# PSU_VCC5V_Buck.net
KiCad netlist of a schematic drawn in Altium Designer
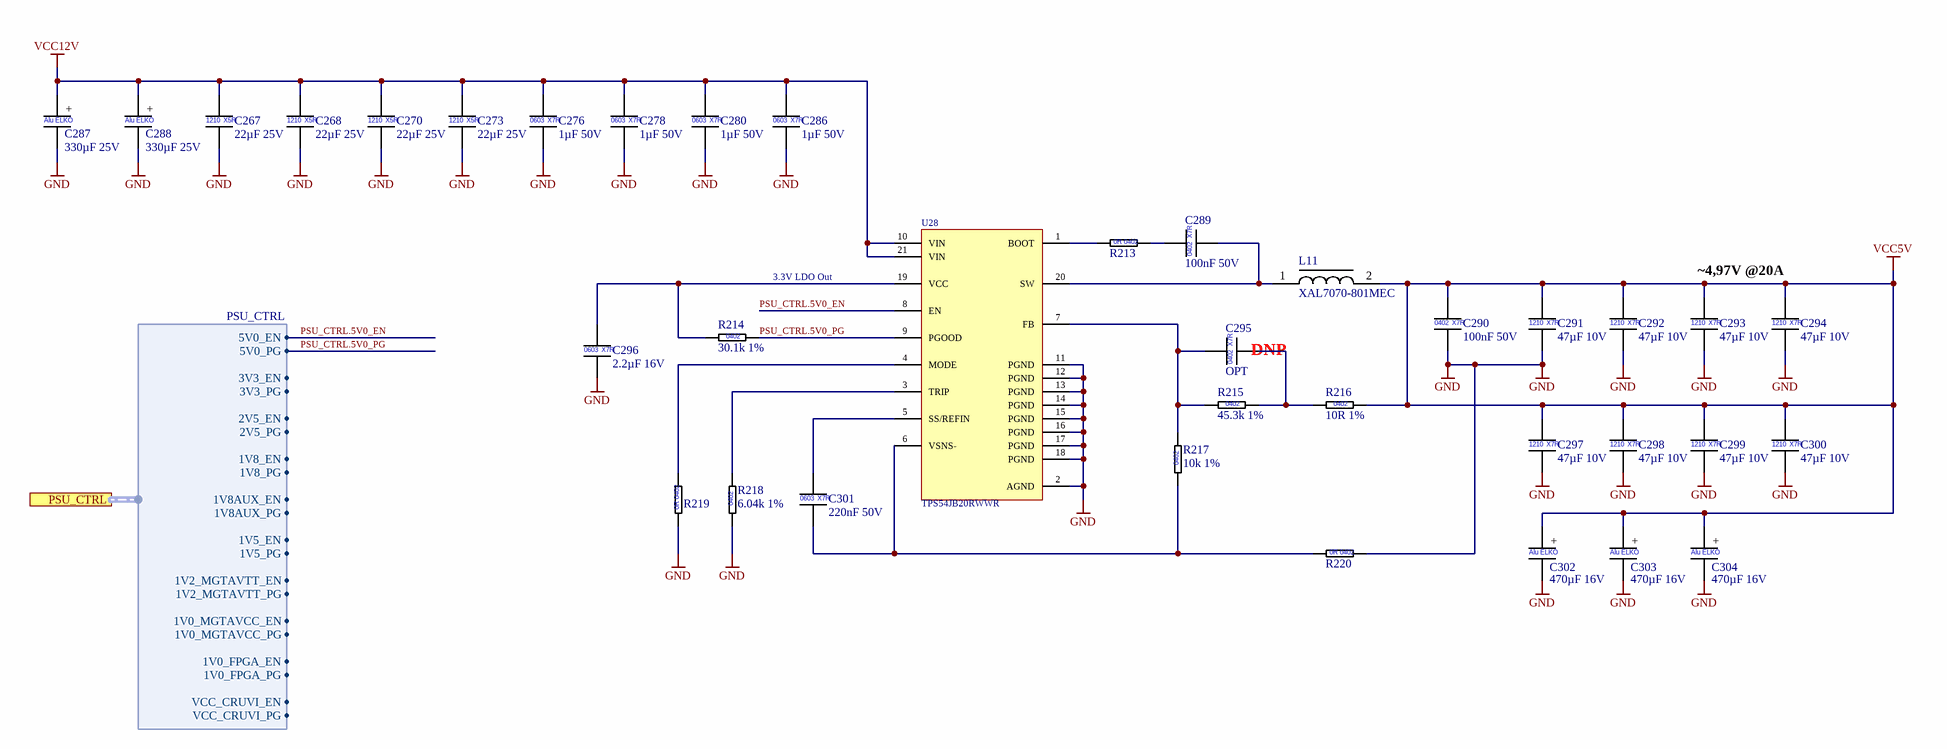
[diagram p0: PSU_VCC5V_Buck.SchDoc]

(export (version "E")
  (design (tool "Eeschema 10.0.6"))
  (components
    (comp (ref "C267")
      (value "22µF 25V")
      (footprint "Cap:CAP_1210")
      (description "Multilayer Ceramic Capacitors MLCC - SMD/SMT 1210 25VDC")
      (libsource (lib "Cap") (part "CAP_1210_22µF_25V"))
    )
    (comp (ref "C268")
      (value "22µF 25V")
      (footprint "Cap:CAP_1210")
      (description "Multilayer Ceramic Capacitors MLCC - SMD/SMT 1210 25VDC")
      (libsource (lib "Cap") (part "CAP_1210_22µF_25V"))
    )
    (comp (ref "C270")
      (value "22µF 25V")
      (footprint "Cap:CAP_1210")
      (description "Multilayer Ceramic Capacitors MLCC - SMD/SMT 1210 25VDC")
      (libsource (lib "Cap") (part "CAP_1210_22µF_25V"))
    )
    (comp (ref "C273")
      (value "22µF 25V")
      (footprint "Cap:CAP_1210")
      (description "Multilayer Ceramic Capacitors MLCC - SMD/SMT 1210 25VDC")
      (libsource (lib "Cap") (part "CAP_1210_22µF_25V"))
    )
    (comp (ref "C276")
      (value "1µF 50V")
      (footprint "CAP_0603")
      (description "Multilayer Ceramic Capacitors MLCC - SMD/SMT 50V 1uF X7R 0603 10%")
      (libsource (lib "Cap") (part "CAP_0603_1µF_50V_X7R_10%"))
    )
    (comp (ref "C278")
      (value "1µF 50V")
      (footprint "CAP_0603")
      (description "Multilayer Ceramic Capacitors MLCC - SMD/SMT 50V 1uF X7R 0603 10%")
      (libsource (lib "Cap") (part "CAP_0603_1µF_50V_X7R_10%"))
    )
    (comp (ref "C280")
      (value "1µF 50V")
      (footprint "CAP_0603")
      (description "Multilayer Ceramic Capacitors MLCC - SMD/SMT 50V 1uF X7R 0603 10%")
      (libsource (lib "Cap") (part "CAP_0603_1µF_50V_X7R_10%"))
    )
    (comp (ref "C286")
      (value "1µF 50V")
      (footprint "CAP_0603")
      (description "Multilayer Ceramic Capacitors MLCC - SMD/SMT 50V 1uF X7R 0603 10%")
      (libsource (lib "Cap") (part "CAP_0603_1µF_50V_X7R_10%"))
    )
    (comp (ref "C287")
      (value "330µF 25V")
      (footprint "Cap:WCAP-PTG5_D10H12.5")
      (description "Organische Polymer-Aluminiumkondensatoren 330uF 25 Volts 20% AEC-Q200")
      (libsource (lib "Cap") (part "CAP_D10L12.5_330µF_25V"))
    )
    (comp (ref "C288")
      (value "330µF 25V")
      (footprint "Cap:WCAP-PTG5_D10H12.5")
      (description "Organische Polymer-Aluminiumkondensatoren 330uF 25 Volts 20% AEC-Q200")
      (libsource (lib "Cap") (part "CAP_D10L12.5_330µF_25V"))
    )
    (comp (ref "C289")
      (value "100nF 50V")
      (footprint "Cap:CAP_0402")
      (description "Multilayer Ceramic Capacitors MLCC - SMD/SMT 0402 50VDC")
      (libsource (lib "") (part "CAP_0402_100nF_50V_1"))
    )
    (comp (ref "C290")
      (value "100nF 50V")
      (footprint "Cap:CAP_0402")
      (description "Multilayer Ceramic Capacitors MLCC - SMD/SMT 0402 50VDC")
      (libsource (lib "Cap") (part "CAP_0402_100nF_50V"))
    )
    (comp (ref "C291")
      (value "47µF 10V")
      (footprint "Cap:CAP_1210")
      (description "Multilayer Ceramic Capacitors MLCC - SMD/SMT 47 uF 10 VDC 10% 1210 X7R")
      (libsource (lib "Cap") (part "CAP_1210_47µF_10V_X7R_10%"))
    )
    (comp (ref "C292")
      (value "47µF 10V")
      (footprint "Cap:CAP_1210")
      (description "Multilayer Ceramic Capacitors MLCC - SMD/SMT 47 uF 10 VDC 10% 1210 X7R")
      (libsource (lib "Cap") (part "CAP_1210_47µF_10V_X7R_10%"))
    )
    (comp (ref "C293")
      (value "47µF 10V")
      (footprint "Cap:CAP_1210")
      (description "Multilayer Ceramic Capacitors MLCC - SMD/SMT 47 uF 10 VDC 10% 1210 X7R")
      (libsource (lib "Cap") (part "CAP_1210_47µF_10V_X7R_10%"))
    )
    (comp (ref "C294")
      (value "47µF 10V")
      (footprint "Cap:CAP_1210")
      (description "Multilayer Ceramic Capacitors MLCC - SMD/SMT 47 uF 10 VDC 10% 1210 X7R")
      (libsource (lib "Cap") (part "CAP_1210_47µF_10V_X7R_10%"))
    )
    (comp (ref "C295")
      (value "OPT")
      (footprint "Cap:CAP_0402")
      (description "Multilayer Ceramic Capacitors MLCC - SMD/SMT 0402 Optional Placeholder")
      (libsource (lib "Cap") (part "CAP_0402_OPT"))
    )
    (comp (ref "C296")
      (value "2.2µF 16V")
      (footprint "Cap:CAP_0603")
      (description "Multilayer Ceramic Capacitors MLCC - SMD/SMT 2.2 uF 16 VDC 10% 0603 X7R")
      (libsource (lib "Cap") (part "CAP_0603_2.2µF_16V_X7R_10%"))
    )
    (comp (ref "C297")
      (value "47µF 10V")
      (footprint "Cap:CAP_1210")
      (description "Multilayer Ceramic Capacitors MLCC - SMD/SMT 47 uF 10 VDC 10% 1210 X7R")
      (libsource (lib "Cap") (part "CAP_1210_47µF_10V_X7R_10%"))
    )
    (comp (ref "C298")
      (value "47µF 10V")
      (footprint "Cap:CAP_1210")
      (description "Multilayer Ceramic Capacitors MLCC - SMD/SMT 47 uF 10 VDC 10% 1210 X7R")
      (libsource (lib "Cap") (part "CAP_1210_47µF_10V_X7R_10%"))
    )
    (comp (ref "C299")
      (value "47µF 10V")
      (footprint "Cap:CAP_1210")
      (description "Multilayer Ceramic Capacitors MLCC - SMD/SMT 47 uF 10 VDC 10% 1210 X7R")
      (libsource (lib "Cap") (part "CAP_1210_47µF_10V_X7R_10%"))
    )
    (comp (ref "C300")
      (value "47µF 10V")
      (footprint "Cap:CAP_1210")
      (description "Multilayer Ceramic Capacitors MLCC - SMD/SMT 47 uF 10 VDC 10% 1210 X7R")
      (libsource (lib "Cap") (part "CAP_1210_47µF_10V_X7R_10%"))
    )
    (comp (ref "C301")
      (value "220nF 50V")
      (footprint "CAP_0603")
      (description "Multilayer Ceramic Capacitors MLCC - SMD/SMT 0.22 uF 50 VDC 10% 0603 X7R")
      (libsource (lib "Cap") (part "CAP_0603_220nF_50V_X7R_10%"))
    )
    (comp (ref "C302")
      (value "470µF 16V")
      (footprint "Cap:WCAP-PTG5_D8H13")
      (description "Organische Polymer-Aluminiumkondensatoren 470uF 16 Volts 20%")
      (libsource (lib "Cap") (part "CAP_D8L9_470µF_16V"))
    )
    (comp (ref "C303")
      (value "470µF 16V")
      (footprint "Cap:WCAP-PTG5_D8H13")
      (description "Organische Polymer-Aluminiumkondensatoren 470uF 16 Volts 20%")
      (libsource (lib "Cap") (part "CAP_D8L9_470µF_16V"))
    )
    (comp (ref "C304")
      (value "470µF 16V")
      (footprint "Cap:WCAP-PTG5_D8H13")
      (description "Organische Polymer-Aluminiumkondensatoren 470uF 16 Volts 20%")
      (libsource (lib "Cap") (part "CAP_D8L9_470µF_16V"))
    )
    (comp (ref "L11")
      (value "XAL7070-801MEC")
      (footprint "indc:COILCRAFT_XAL7070")
      (description "Power Inductors - SMD 800nH Shld 20% 25.8A 2.29mOhms AECQ200")
      (libsource (lib "Indc") (part "XAL7070-801MEC_Power Inductors SMD 800nH Shld 20% 25.8A 2.29mOhms AECQ200"))
    )
    (comp (ref "R213")
      (value "0R Jumper")
      (footprint "res:RES_0402")
      (description "Thick Film Resistors - SMD 0Ohm")
      (libsource (lib "Res") (part "RES_0402_0R Jumper"))
    )
    (comp (ref "R214")
      (value "30.1k 1%")
      (footprint "res:RES_0402")
      (description "Thick Film Resistors - SMD 30.1kOhm 1%")
      (libsource (lib "Res") (part "RES_0402_30.1k_1%"))
    )
    (comp (ref "R215")
      (value "45.3k 1%")
      (footprint "res:RES_0402")
      (description "Thick Film Resistors - SMD 45.3kOhm 1%")
      (libsource (lib "Res") (part "RES_0402_45.3k_1%"))
    )
    (comp (ref "R216")
      (value "10R 1%")
      (footprint "res:RES_0402")
      (description "Thick Film Resistors - SMD 10Ohm 1%")
      (libsource (lib "Res") (part "RES_0402_10R_1%"))
    )
    (comp (ref "R217")
      (value "10k 1%")
      (footprint "Res:RES_0402")
      (description "Thick Film Resistors - SMD 10kOhm 1%")
      (libsource (lib "Res") (part "RES_0402_10k_1%"))
    )
    (comp (ref "R218")
      (value "6.04k 1%")
      (footprint "Res:RES_0402")
      (description "Thick Film Resistors - SMD 6.04kOhm 1%")
      (libsource (lib "Res") (part "RES_0402_6.04k_1%"))
    )
    (comp (ref "R219")
      (value "0R Jumper")
      (footprint "res:RES_0402")
      (description "Thick Film Resistors - SMD 0Ohm")
      (libsource (lib "Res") (part "RES_0402_0R Jumper"))
    )
    (comp (ref "R220")
      (value "0R Jumper")
      (footprint "res:RES_0402")
      (description "Thick Film Resistors - SMD 0Ohm")
      (libsource (lib "Res") (part "RES_0402_0R Jumper"))
    )
    (comp (ref "U28")
      (value "TPS54JB20RWWR")
      (footprint "power:VQFN-HR21_RWW0021A")
      (description "Switching Voltage Regulators 2.7-V to 16-V input 20-A synchronous Buck")
      (libsource (lib "Power") (part "TPS54JB20RWWR_Switching Voltage Regulators 2.7-V to 16-V input 20-A synchronous Buck"))
    )
  )
  (nets
    (net (code "2") (name "/PSU_CTRL.5V0_EN") (class "Default")
      (node (ref "U28") (pin "8") (pinfunction "EN_8") (pintype "passive"))
    )
    (net (code "3") (name "/PSU_CTRL.5V0_PG") (class "Default")
      (node (ref "R214") (pin "2") (pinfunction "2_2") (pintype "passive"))
      (node (ref "U28") (pin "9") (pinfunction "PGOOD_9") (pintype "passive"))
    )
    (net (code "5") (name "GND") (class "Default")
      (node (ref "C267") (pin "2") (pinfunction "2_2") (pintype "passive"))
      (node (ref "C268") (pin "2") (pinfunction "2_2") (pintype "passive"))
      (node (ref "C270") (pin "2") (pinfunction "2_2") (pintype "passive"))
      (node (ref "C273") (pin "2") (pinfunction "2_2") (pintype "passive"))
      (node (ref "C276") (pin "2") (pinfunction "2_2") (pintype "passive"))
      (node (ref "C278") (pin "2") (pinfunction "2_2") (pintype "passive"))
      (node (ref "C280") (pin "2") (pinfunction "2_2") (pintype "passive"))
      (node (ref "C286") (pin "2") (pinfunction "2_2") (pintype "passive"))
      (node (ref "C287") (pin "2") (pinfunction "2_2") (pintype "passive"))
      (node (ref "C288") (pin "2") (pinfunction "2_2") (pintype "passive"))
      (node (ref "C290") (pin "2") (pinfunction "2_2") (pintype "passive"))
      (node (ref "C291") (pin "2") (pinfunction "2_2") (pintype "passive"))
      (node (ref "C292") (pin "2") (pinfunction "2_2") (pintype "passive"))
      (node (ref "C293") (pin "2") (pinfunction "2_2") (pintype "passive"))
      (node (ref "C294") (pin "2") (pinfunction "2_2") (pintype "passive"))
      (node (ref "C296") (pin "2") (pinfunction "2_2") (pintype "passive"))
      (node (ref "C297") (pin "2") (pinfunction "2_2") (pintype "passive"))
      (node (ref "C298") (pin "2") (pinfunction "2_2") (pintype "passive"))
      (node (ref "C299") (pin "2") (pinfunction "2_2") (pintype "passive"))
      (node (ref "C300") (pin "2") (pinfunction "2_2") (pintype "passive"))
      (node (ref "C302") (pin "2") (pinfunction "2_2") (pintype "passive"))
      (node (ref "C303") (pin "2") (pinfunction "2_2") (pintype "passive"))
      (node (ref "C304") (pin "2") (pinfunction "2_2") (pintype "passive"))
      (node (ref "R218") (pin "1") (pinfunction "1_1") (pintype "passive"))
      (node (ref "R219") (pin "1") (pinfunction "1_1") (pintype "passive"))
      (node (ref "R220") (pin "2") (pinfunction "2_2") (pintype "passive"))
      (node (ref "U28") (pin "11") (pinfunction "PGND_11") (pintype "passive"))
      (node (ref "U28") (pin "12") (pinfunction "PGND_12") (pintype "passive"))
      (node (ref "U28") (pin "13") (pinfunction "PGND_13") (pintype "passive"))
      (node (ref "U28") (pin "14") (pinfunction "PGND_14") (pintype "passive"))
      (node (ref "U28") (pin "15") (pinfunction "PGND_15") (pintype "passive"))
      (node (ref "U28") (pin "16") (pinfunction "PGND_16") (pintype "passive"))
      (node (ref "U28") (pin "17") (pinfunction "PGND_17") (pintype "passive"))
      (node (ref "U28") (pin "18") (pinfunction "PGND_18") (pintype "passive"))
      (node (ref "U28") (pin "2") (pinfunction "AGND_2") (pintype "passive"))
    )
    (net (code "6") (name "Net-(C289-Pad1)") (class "Default")
      (node (ref "C289") (pin "1") (pinfunction "1_1") (pintype "passive"))
      (node (ref "R213") (pin "2") (pinfunction "2_2") (pintype "passive"))
    )
    (net (code "7") (name "Net-(C295-Pad2)") (class "Default")
      (node (ref "C295") (pin "2") (pinfunction "2_2") (pintype "passive"))
      (node (ref "R215") (pin "2") (pinfunction "2_2") (pintype "passive"))
      (node (ref "R216") (pin "1") (pinfunction "1_1") (pintype "passive"))
    )
    (net (code "8") (name "Net-(U28-BOOT)") (class "Default")
      (node (ref "R213") (pin "1") (pinfunction "1_1") (pintype "passive"))
      (node (ref "U28") (pin "1") (pinfunction "BOOT_1") (pintype "passive"))
    )
    (net (code "9") (name "Net-(U28-FB)") (class "Default")
      (node (ref "C295") (pin "1") (pinfunction "1_1") (pintype "passive"))
      (node (ref "R215") (pin "1") (pinfunction "1_1") (pintype "passive"))
      (node (ref "R217") (pin "2") (pinfunction "2_2") (pintype "passive"))
      (node (ref "U28") (pin "7") (pinfunction "FB_7") (pintype "passive"))
    )
    (net (code "10") (name "Net-(U28-MODE)") (class "Default")
      (node (ref "R219") (pin "2") (pinfunction "2_2") (pintype "passive"))
      (node (ref "U28") (pin "4") (pinfunction "MODE_4") (pintype "passive"))
    )
    (net (code "11") (name "Net-(U28-SS{slash}REFIN)") (class "Default")
      (node (ref "C301") (pin "1") (pinfunction "1_1") (pintype "passive"))
      (node (ref "U28") (pin "5") (pinfunction "SS/REFIN_5") (pintype "passive"))
    )
    (net (code "12") (name "Net-(U28-SW)") (class "Default")
      (node (ref "C289") (pin "2") (pinfunction "2_2") (pintype "passive"))
      (node (ref "L11") (pin "1") (pinfunction "1_1") (pintype "passive"))
      (node (ref "U28") (pin "20") (pinfunction "SW_20") (pintype "passive"))
    )
    (net (code "13") (name "Net-(U28-TRIP)") (class "Default")
      (node (ref "R218") (pin "2") (pinfunction "2_2") (pintype "passive"))
      (node (ref "U28") (pin "3") (pinfunction "TRIP_3") (pintype "passive"))
    )
    (net (code "14") (name "Net-(U28-VCC)") (class "Default")
      (node (ref "C296") (pin "1") (pinfunction "1_1") (pintype "passive"))
      (node (ref "R214") (pin "1") (pinfunction "1_1") (pintype "passive"))
      (node (ref "U28") (pin "19") (pinfunction "VCC_19") (pintype "passive"))
    )
    (net (code "15") (name "Net-(U28-VSNS-)") (class "Default")
      (node (ref "C301") (pin "2") (pinfunction "2_2") (pintype "passive"))
      (node (ref "R217") (pin "1") (pinfunction "1_1") (pintype "passive"))
      (node (ref "R220") (pin "1") (pinfunction "1_1") (pintype "passive"))
      (node (ref "U28") (pin "6") (pinfunction "VSNS-_6") (pintype "passive"))
    )
    (net (code "16") (name "VCC5V") (class "Default")
      (node (ref "C290") (pin "1") (pinfunction "1_1") (pintype "passive"))
      (node (ref "C291") (pin "1") (pinfunction "1_1") (pintype "passive"))
      (node (ref "C292") (pin "1") (pinfunction "1_1") (pintype "passive"))
      (node (ref "C293") (pin "1") (pinfunction "1_1") (pintype "passive"))
      (node (ref "C294") (pin "1") (pinfunction "1_1") (pintype "passive"))
      (node (ref "C297") (pin "1") (pinfunction "1_1") (pintype "passive"))
      (node (ref "C298") (pin "1") (pinfunction "1_1") (pintype "passive"))
      (node (ref "C299") (pin "1") (pinfunction "1_1") (pintype "passive"))
      (node (ref "C300") (pin "1") (pinfunction "1_1") (pintype "passive"))
      (node (ref "C302") (pin "1") (pinfunction "1_1") (pintype "passive"))
      (node (ref "C303") (pin "1") (pinfunction "1_1") (pintype "passive"))
      (node (ref "C304") (pin "1") (pinfunction "1_1") (pintype "passive"))
      (node (ref "L11") (pin "2") (pinfunction "2_2") (pintype "passive"))
      (node (ref "R216") (pin "2") (pinfunction "2_2") (pintype "passive"))
    )
    (net (code "17") (name "VCC12V") (class "Default")
      (node (ref "C267") (pin "1") (pinfunction "1_1") (pintype "passive"))
      (node (ref "C268") (pin "1") (pinfunction "1_1") (pintype "passive"))
      (node (ref "C270") (pin "1") (pinfunction "1_1") (pintype "passive"))
      (node (ref "C273") (pin "1") (pinfunction "1_1") (pintype "passive"))
      (node (ref "C276") (pin "1") (pinfunction "1_1") (pintype "passive"))
      (node (ref "C278") (pin "1") (pinfunction "1_1") (pintype "passive"))
      (node (ref "C280") (pin "1") (pinfunction "1_1") (pintype "passive"))
      (node (ref "C286") (pin "1") (pinfunction "1_1") (pintype "passive"))
      (node (ref "C287") (pin "1") (pinfunction "1_1") (pintype "passive"))
      (node (ref "C288") (pin "1") (pinfunction "1_1") (pintype "passive"))
      (node (ref "U28") (pin "10") (pinfunction "VIN_10") (pintype "passive"))
      (node (ref "U28") (pin "21") (pinfunction "VIN_21") (pintype "passive"))
    )
  )
)
